# LEDBatterychargeIndicatorCircuit.net
KiCad netlist of a schematic drawn in EAGLE
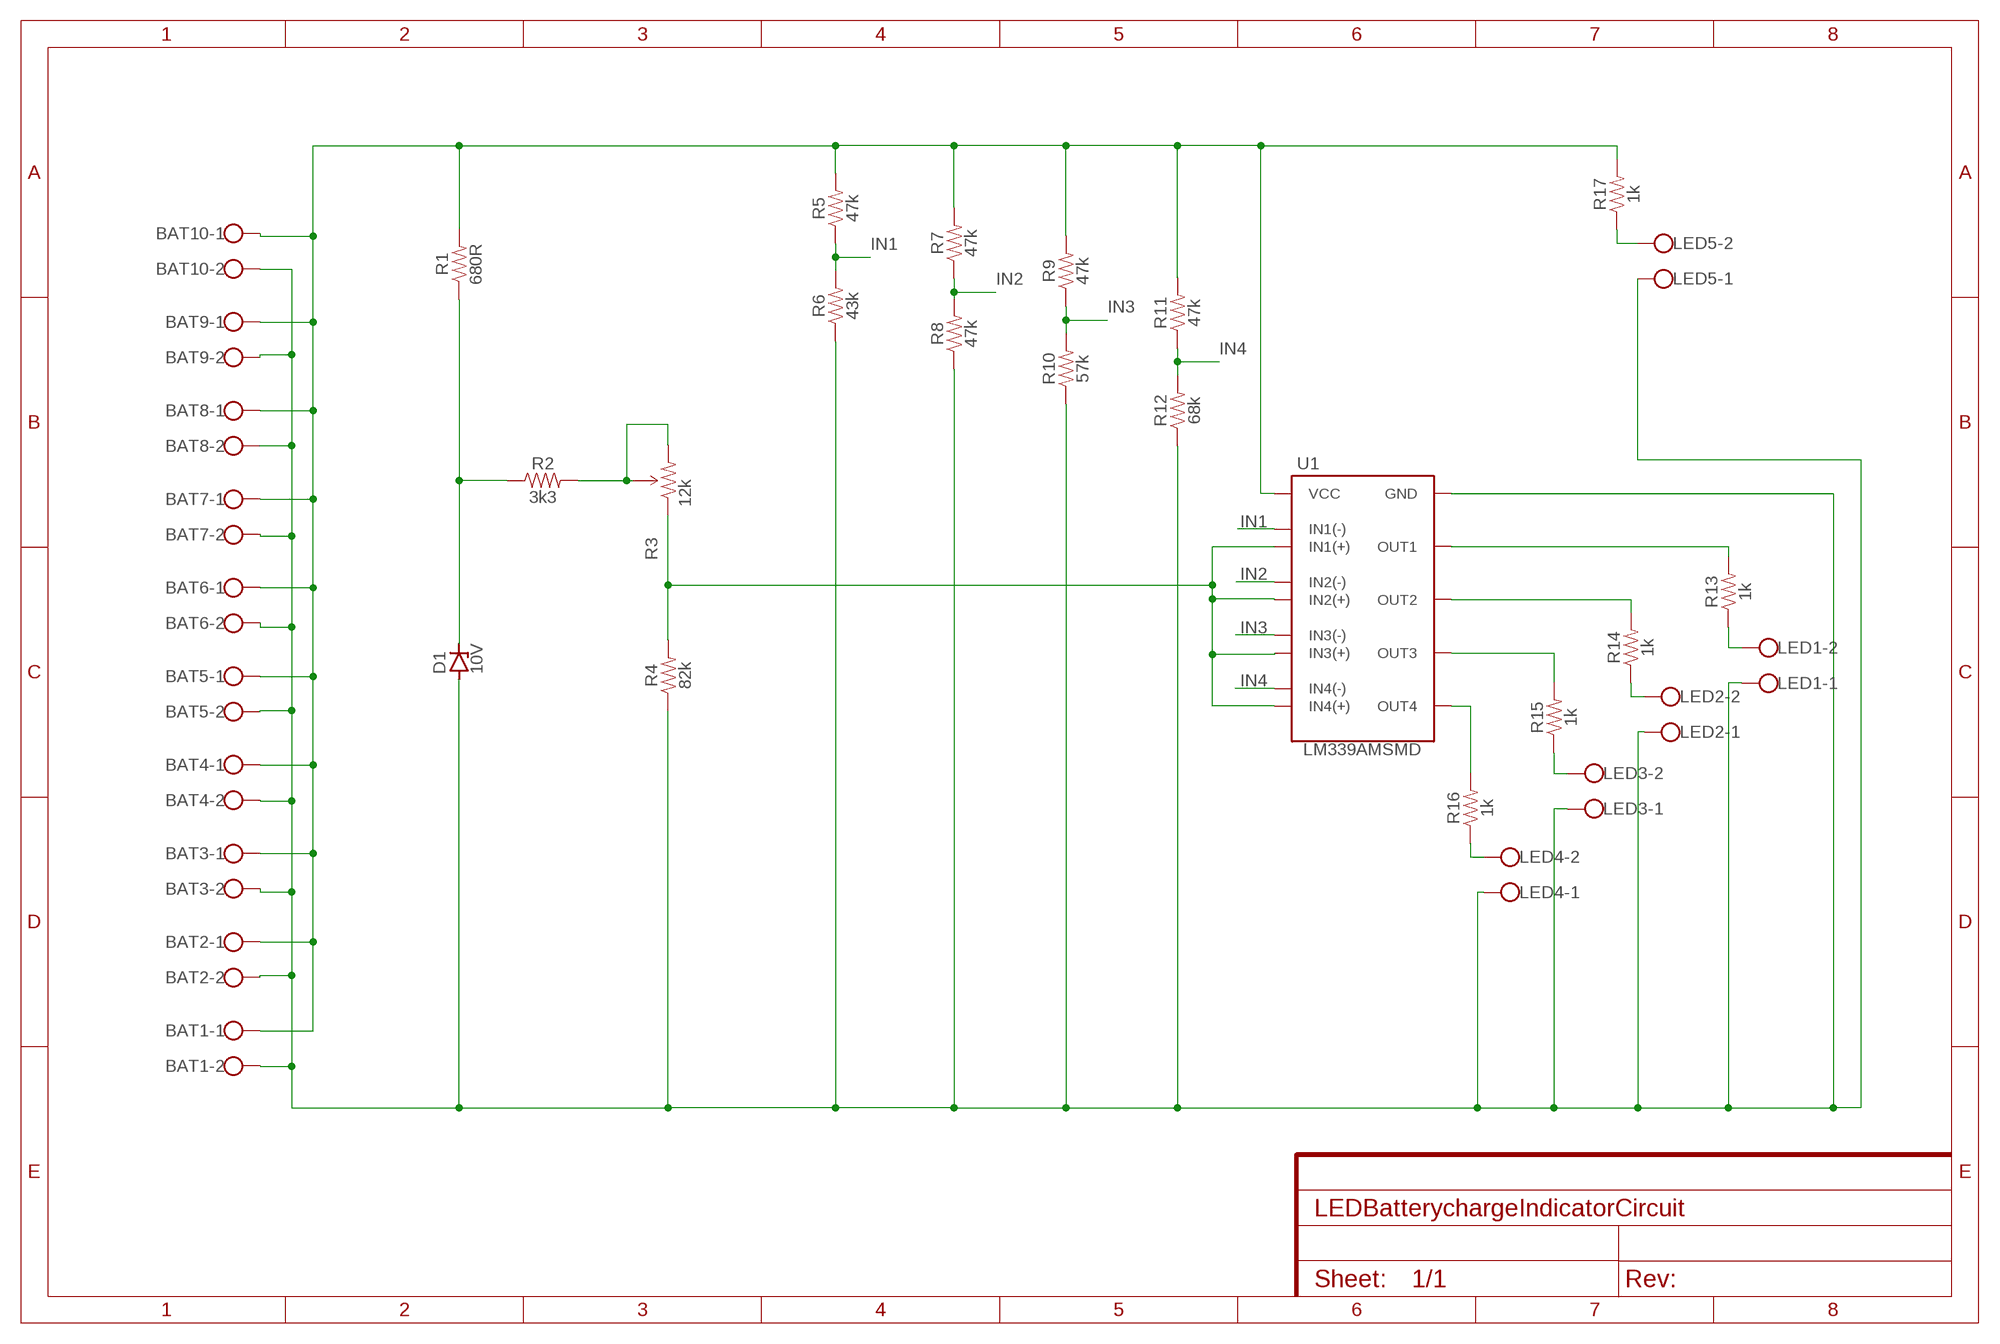
[diagram p0: schematic, sheet 1]

(export (version "E")
  (design (tool "Eeschema 10.0.6"))
  (components
    (comp (ref "BAT1")
      (value "W237-102")
      (footprint "eagle-import:W237-102")
      (fields (field (name "MPN") "237-102"))
      (libsource (lib "eagle-import") (part "W237-102"))
    )
    (comp (ref "BAT2")
      (value "W237-102")
      (footprint "eagle-import:W237-102")
      (fields (field (name "MPN") "237-102"))
      (libsource (lib "eagle-import") (part "W237-102"))
    )
    (comp (ref "BAT3")
      (value "W237-102")
      (footprint "eagle-import:W237-102")
      (fields (field (name "MPN") "237-102"))
      (libsource (lib "eagle-import") (part "W237-102"))
    )
    (comp (ref "BAT4")
      (value "W237-102")
      (footprint "eagle-import:W237-102")
      (fields (field (name "MPN") "237-102"))
      (libsource (lib "eagle-import") (part "W237-102"))
    )
    (comp (ref "BAT5")
      (value "W237-102")
      (footprint "eagle-import:W237-102")
      (fields (field (name "MPN") "237-102"))
      (libsource (lib "eagle-import") (part "W237-102"))
    )
    (comp (ref "BAT6")
      (value "W237-102")
      (footprint "eagle-import:W237-102")
      (fields (field (name "MPN") "237-102"))
      (libsource (lib "eagle-import") (part "W237-102"))
    )
    (comp (ref "BAT7")
      (value "W237-102")
      (footprint "eagle-import:W237-102")
      (fields (field (name "MPN") "237-102"))
      (libsource (lib "eagle-import") (part "W237-102"))
    )
    (comp (ref "BAT8")
      (value "W237-102")
      (footprint "eagle-import:W237-102")
      (fields (field (name "MPN") "237-102"))
      (libsource (lib "eagle-import") (part "W237-102"))
    )
    (comp (ref "BAT9")
      (value "W237-102")
      (footprint "eagle-import:W237-102")
      (fields (field (name "MPN") "237-102"))
      (libsource (lib "eagle-import") (part "W237-102"))
    )
    (comp (ref "BAT10")
      (value "W237-102")
      (footprint "eagle-import:W237-102")
      (fields (field (name "MPN") "237-102"))
      (libsource (lib "eagle-import") (part "W237-102"))
    )
    (comp (ref "D1")
      (value "10V")
      (footprint "eagle-import:F126Z12")
      (libsource (lib "eagle-import") (part "ZENER-DIODEF126-12"))
    )
    (comp (ref "LED1")
      (value "W237-102")
      (footprint "eagle-import:W237-102")
      (fields (field (name "MPN") "237-102"))
      (libsource (lib "eagle-import") (part "W237-102"))
    )
    (comp (ref "LED2")
      (value "W237-102")
      (footprint "eagle-import:W237-102")
      (fields (field (name "MPN") "237-102"))
      (libsource (lib "eagle-import") (part "W237-102"))
    )
    (comp (ref "LED3")
      (value "W237-102")
      (footprint "eagle-import:W237-102")
      (fields (field (name "MPN") "237-102"))
      (libsource (lib "eagle-import") (part "W237-102"))
    )
    (comp (ref "LED4")
      (value "W237-102")
      (footprint "eagle-import:W237-102")
      (fields (field (name "MPN") "237-102"))
      (libsource (lib "eagle-import") (part "W237-102"))
    )
    (comp (ref "LED5")
      (value "W237-102")
      (footprint "eagle-import:W237-102")
      (fields (field (name "MPN") "237-102"))
      (libsource (lib "eagle-import") (part "W237-102"))
    )
    (comp (ref "R1")
      (value "680R")
      (footprint "eagle-import:0805")
      (libsource (lib "eagle-import") (part "RESISTOR0805"))
    )
    (comp (ref "R2")
      (value "3k3")
      (footprint "eagle-import:0805")
      (libsource (lib "eagle-import") (part "RESISTOR0805"))
    )
    (comp (ref "R3")
      (value "12k")
      (footprint "eagle-import:TRIM_POT_PTH")
      (libsource (lib "eagle-import") (part "TRIMPOTPTH"))
    )
    (comp (ref "R4")
      (value "82k")
      (footprint "eagle-import:0805")
      (libsource (lib "eagle-import") (part "RESISTOR0805"))
    )
    (comp (ref "R5")
      (value "47k")
      (footprint "eagle-import:0805")
      (libsource (lib "eagle-import") (part "RESISTOR0805"))
    )
    (comp (ref "R6")
      (value "43k")
      (footprint "eagle-import:0805")
      (libsource (lib "eagle-import") (part "RESISTOR0805"))
    )
    (comp (ref "R7")
      (value "47k")
      (footprint "eagle-import:0805")
      (libsource (lib "eagle-import") (part "RESISTOR0805"))
    )
    (comp (ref "R8")
      (value "47k")
      (footprint "eagle-import:0805")
      (libsource (lib "eagle-import") (part "RESISTOR0805"))
    )
    (comp (ref "R9")
      (value "47k")
      (footprint "eagle-import:0805")
      (libsource (lib "eagle-import") (part "RESISTOR0805"))
    )
    (comp (ref "R10")
      (value "57k")
      (footprint "eagle-import:0805")
      (libsource (lib "eagle-import") (part "RESISTOR0805"))
    )
    (comp (ref "R11")
      (value "47k")
      (footprint "eagle-import:0805")
      (libsource (lib "eagle-import") (part "RESISTOR0805"))
    )
    (comp (ref "R12")
      (value "68k")
      (footprint "eagle-import:0805")
      (libsource (lib "eagle-import") (part "RESISTOR0805"))
    )
    (comp (ref "R13")
      (value "1k")
      (footprint "eagle-import:0805")
      (libsource (lib "eagle-import") (part "RESISTOR0805"))
    )
    (comp (ref "R14")
      (value "1k")
      (footprint "eagle-import:0805")
      (libsource (lib "eagle-import") (part "RESISTOR0805"))
    )
    (comp (ref "R15")
      (value "1k")
      (footprint "eagle-import:0805")
      (libsource (lib "eagle-import") (part "RESISTOR0805"))
    )
    (comp (ref "R16")
      (value "1k")
      (footprint "eagle-import:0805")
      (libsource (lib "eagle-import") (part "RESISTOR0805"))
    )
    (comp (ref "R17")
      (value "1k")
      (footprint "eagle-import:0805")
      (libsource (lib "eagle-import") (part "RESISTOR0805"))
    )
    (comp (ref "U1")
      (value "LM339AMSMD")
      (footprint "eagle-import:LM339AM")
      (libsource (lib "eagle-import") (part "LM339AMSMD"))
    )
  )
  (nets
    (net (code "1") (name "/IN1") (class "Default")
      (node (ref "R5") (pin "1") (pinfunction "1_1") (pintype "passive"))
      (node (ref "R6") (pin "2") (pinfunction "2_2") (pintype "passive"))
      (node (ref "U1") (pin "4") (pinfunction "IN1(-)_4") (pintype "input"))
    )
    (net (code "2") (name "/IN2") (class "Default")
      (node (ref "R7") (pin "1") (pinfunction "1_1") (pintype "passive"))
      (node (ref "R8") (pin "2") (pinfunction "2_2") (pintype "passive"))
      (node (ref "U1") (pin "6") (pinfunction "IN2(-)_6") (pintype "input"))
    )
    (net (code "3") (name "/IN3") (class "Default")
      (node (ref "R10") (pin "2") (pinfunction "2_2") (pintype "passive"))
      (node (ref "R9") (pin "1") (pinfunction "1_1") (pintype "passive"))
      (node (ref "U1") (pin "8") (pinfunction "IN3(-)_8") (pintype "input"))
    )
    (net (code "4") (name "/IN4") (class "Default")
      (node (ref "R11") (pin "1") (pinfunction "1_1") (pintype "passive"))
      (node (ref "R12") (pin "2") (pinfunction "2_2") (pintype "passive"))
      (node (ref "U1") (pin "10") (pinfunction "IN4(-)_10") (pintype "input"))
    )
    (net (code "5") (name "Net-(BAT10A-KL)") (class "Default")
      (node (ref "BAT1") (pin "1") (pinfunction "KL_1") (pintype "passive"))
      (node (ref "BAT10") (pin "1") (pinfunction "KL_1") (pintype "passive"))
      (node (ref "BAT2") (pin "1") (pinfunction "KL_1") (pintype "passive"))
      (node (ref "BAT3") (pin "1") (pinfunction "KL_1") (pintype "passive"))
      (node (ref "BAT4") (pin "1") (pinfunction "KL_1") (pintype "passive"))
      (node (ref "BAT5") (pin "1") (pinfunction "KL_1") (pintype "passive"))
      (node (ref "BAT6") (pin "1") (pinfunction "KL_1") (pintype "passive"))
      (node (ref "BAT7") (pin "1") (pinfunction "KL_1") (pintype "passive"))
      (node (ref "BAT8") (pin "1") (pinfunction "KL_1") (pintype "passive"))
      (node (ref "BAT9") (pin "1") (pinfunction "KL_1") (pintype "passive"))
      (node (ref "R1") (pin "2") (pinfunction "2_2") (pintype "passive"))
      (node (ref "R11") (pin "2") (pinfunction "2_2") (pintype "passive"))
      (node (ref "R17") (pin "2") (pinfunction "2_2") (pintype "passive"))
      (node (ref "R5") (pin "2") (pinfunction "2_2") (pintype "passive"))
      (node (ref "R7") (pin "2") (pinfunction "2_2") (pintype "passive"))
      (node (ref "R9") (pin "2") (pinfunction "2_2") (pintype "passive"))
      (node (ref "U1") (pin "3") (pinfunction "VCC_3") (pintype "power_in"))
    )
    (net (code "6") (name "Net-(BAT10B-KL)") (class "Default")
      (node (ref "BAT1") (pin "2") (pinfunction "KL_2") (pintype "passive"))
      (node (ref "BAT10") (pin "2") (pinfunction "KL_2") (pintype "passive"))
      (node (ref "BAT2") (pin "2") (pinfunction "KL_2") (pintype "passive"))
      (node (ref "BAT3") (pin "2") (pinfunction "KL_2") (pintype "passive"))
      (node (ref "BAT4") (pin "2") (pinfunction "KL_2") (pintype "passive"))
      (node (ref "BAT5") (pin "2") (pinfunction "KL_2") (pintype "passive"))
      (node (ref "BAT6") (pin "2") (pinfunction "KL_2") (pintype "passive"))
      (node (ref "BAT7") (pin "2") (pinfunction "KL_2") (pintype "passive"))
      (node (ref "BAT8") (pin "2") (pinfunction "KL_2") (pintype "passive"))
      (node (ref "BAT9") (pin "2") (pinfunction "KL_2") (pintype "passive"))
      (node (ref "D1") (pin "A") (pinfunction "A_A") (pintype "passive"))
      (node (ref "LED1") (pin "1") (pinfunction "KL_1") (pintype "passive"))
      (node (ref "LED2") (pin "1") (pinfunction "KL_1") (pintype "passive"))
      (node (ref "LED3") (pin "1") (pinfunction "KL_1") (pintype "passive"))
      (node (ref "LED4") (pin "1") (pinfunction "KL_1") (pintype "passive"))
      (node (ref "LED5") (pin "1") (pinfunction "KL_1") (pintype "passive"))
      (node (ref "R10") (pin "1") (pinfunction "1_1") (pintype "passive"))
      (node (ref "R12") (pin "1") (pinfunction "1_1") (pintype "passive"))
      (node (ref "R4") (pin "1") (pinfunction "1_1") (pintype "passive"))
      (node (ref "R6") (pin "1") (pinfunction "1_1") (pintype "passive"))
      (node (ref "R8") (pin "1") (pinfunction "1_1") (pintype "passive"))
      (node (ref "U1") (pin "12") (pinfunction "GND_12") (pintype "power_in"))
    )
    (net (code "7") (name "Net-(D1-PadC)") (class "Default")
      (node (ref "D1") (pin "C") (pinfunction "C_C") (pintype "passive"))
      (node (ref "R1") (pin "1") (pinfunction "1_1") (pintype "passive"))
      (node (ref "R2") (pin "1") (pinfunction "1_1") (pintype "passive"))
    )
    (net (code "8") (name "Net-(LED1B-KL)") (class "Default")
      (node (ref "LED1") (pin "2") (pinfunction "KL_2") (pintype "passive"))
      (node (ref "R13") (pin "1") (pinfunction "1_1") (pintype "passive"))
    )
    (net (code "9") (name "Net-(LED2B-KL)") (class "Default")
      (node (ref "LED2") (pin "2") (pinfunction "KL_2") (pintype "passive"))
      (node (ref "R14") (pin "1") (pinfunction "1_1") (pintype "passive"))
    )
    (net (code "10") (name "Net-(LED3B-KL)") (class "Default")
      (node (ref "LED3") (pin "2") (pinfunction "KL_2") (pintype "passive"))
      (node (ref "R15") (pin "1") (pinfunction "1_1") (pintype "passive"))
    )
    (net (code "11") (name "Net-(LED4B-KL)") (class "Default")
      (node (ref "LED4") (pin "2") (pinfunction "KL_2") (pintype "passive"))
      (node (ref "R16") (pin "1") (pinfunction "1_1") (pintype "passive"))
    )
    (net (code "12") (name "Net-(LED5B-KL)") (class "Default")
      (node (ref "LED5") (pin "2") (pinfunction "KL_2") (pintype "passive"))
      (node (ref "R17") (pin "1") (pinfunction "1_1") (pintype "passive"))
    )
    (net (code "13") (name "Net-(R3-CCW)") (class "Default")
      (node (ref "R3") (pin "1") (pinfunction "CCW_1") (pintype "passive"))
      (node (ref "R4") (pin "2") (pinfunction "2_2") (pintype "passive"))
      (node (ref "U1") (pin "11") (pinfunction "IN4(+)_11") (pintype "input"))
      (node (ref "U1") (pin "5") (pinfunction "IN1(+)_5") (pintype "input"))
      (node (ref "U1") (pin "7") (pinfunction "IN2(+)_7") (pintype "input"))
      (node (ref "U1") (pin "9") (pinfunction "IN3(+)_9") (pintype "input"))
    )
    (net (code "14") (name "Net-(R3-CW)") (class "Default")
      (node (ref "R2") (pin "2") (pinfunction "2_2") (pintype "passive"))
      (node (ref "R3") (pin "2") (pinfunction "WIPER_2") (pintype "passive"))
      (node (ref "R3") (pin "3") (pinfunction "CW_3") (pintype "passive"))
    )
    (net (code "15") (name "Net-(U1-OUT1)") (class "Default")
      (node (ref "R13") (pin "2") (pinfunction "2_2") (pintype "passive"))
      (node (ref "U1") (pin "2") (pinfunction "OUT1_2") (pintype "output"))
    )
    (net (code "16") (name "Net-(U1-OUT2)") (class "Default")
      (node (ref "R14") (pin "2") (pinfunction "2_2") (pintype "passive"))
      (node (ref "U1") (pin "1") (pinfunction "OUT2_1") (pintype "output"))
    )
    (net (code "17") (name "Net-(U1-OUT3)") (class "Default")
      (node (ref "R15") (pin "2") (pinfunction "2_2") (pintype "passive"))
      (node (ref "U1") (pin "14") (pinfunction "OUT3_14") (pintype "output"))
    )
    (net (code "18") (name "Net-(U1-OUT4)") (class "Default")
      (node (ref "R16") (pin "2") (pinfunction "2_2") (pintype "passive"))
      (node (ref "U1") (pin "13") (pinfunction "OUT4_13") (pintype "output"))
    )
  )
)
